# basic.net
KiCad netlist of a schematic drawn in EAGLE
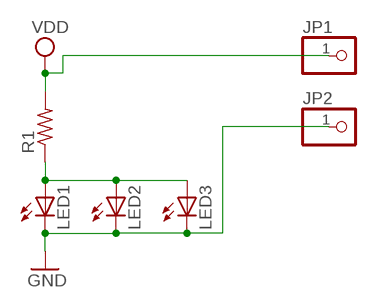
[diagram p0: schematic, sheet 1]

(export (version "E")
  (design (tool "Eeschema 10.0.6"))
  (components
    (comp (ref "JP1")
      (value "PINHD-1X1")
      (footprint "eagle-import:1X01")
      (libsource (lib "eagle-import") (part "PINHD-1X1"))
    )
    (comp (ref "JP2")
      (value "PINHD-1X1")
      (footprint "eagle-import:1X01")
      (libsource (lib "eagle-import") (part "PINHD-1X1"))
    )
    (comp (ref "LED1")
      (value "LED5MM")
      (footprint "eagle-import:LED5MM")
      (libsource (lib "eagle-import") (part "LED5MM"))
    )
    (comp (ref "LED2")
      (value "LED5MM")
      (footprint "eagle-import:LED5MM")
      (libsource (lib "eagle-import") (part "LED5MM"))
    )
    (comp (ref "LED3")
      (value "LED5MM")
      (footprint "eagle-import:LED5MM")
      (libsource (lib "eagle-import") (part "LED5MM"))
    )
    (comp (ref "R1")
      (value "R-US_0204/2V")
      (footprint "eagle-import:0204V")
      (libsource (lib "eagle-import") (part "R-US_0204/2V"))
    )
  )
  (nets
    (net (code "1") (name "GND") (class "Default")
      (node (ref "JP2") (pin "1") (pinfunction "1_1") (pintype "passive"))
      (node (ref "LED1") (pin "K") (pinfunction "C_K") (pintype "passive"))
      (node (ref "LED2") (pin "K") (pinfunction "C_K") (pintype "passive"))
      (node (ref "LED3") (pin "K") (pinfunction "C_K") (pintype "passive"))
    )
    (net (code "2") (name "Net-(LED1-PadA)") (class "Default")
      (node (ref "LED1") (pin "A") (pinfunction "A_A") (pintype "passive"))
      (node (ref "LED2") (pin "A") (pinfunction "A_A") (pintype "passive"))
      (node (ref "LED3") (pin "A") (pinfunction "A_A") (pintype "passive"))
      (node (ref "R1") (pin "1") (pinfunction "1_1") (pintype "passive"))
    )
    (net (code "3") (name "VDD") (class "Default")
      (node (ref "JP1") (pin "1") (pinfunction "1_1") (pintype "passive"))
      (node (ref "R1") (pin "2") (pinfunction "2_2") (pintype "passive"))
    )
  )
)
